# USB.net
KiCad netlist of a schematic drawn in Altium Designer
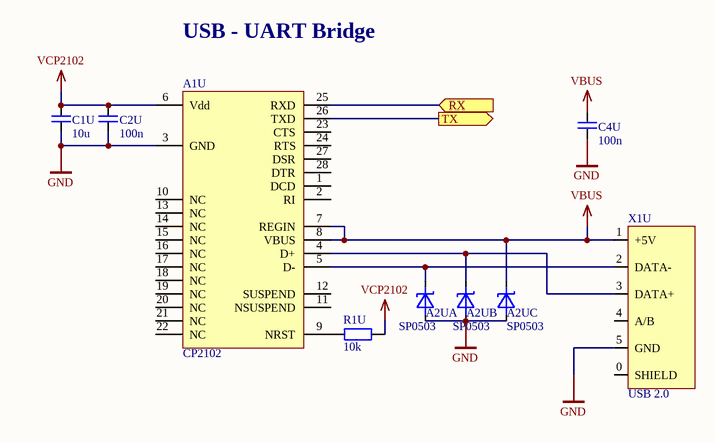
[diagram p0: USB.SchDoc]

(export (version "E")
  (design (tool "Eeschema 10.0.6"))
  (components
    (comp (ref "A1U")
      (value "CP2102")
      (footprint "QFN28")
      (description "USB-UART Bridge")
      (libsource (lib "IC") (part "CP2102"))
    )
    (comp (ref "A2U")
      (value "SP0503")
      (footprint "SOT143-4")
      (description "ESD Suppressors")
      (libsource (lib "IC") (part "SP0503"))
    )
    (comp (ref "C1U") (value "10u") (footprint "0805") (libsource (lib "Passive") (part "Kondensator")))
    (comp (ref "C2U") (value "100n") (footprint "0805") (libsource (lib "Passive") (part "Kondensator")))
    (comp (ref "C4U") (value "100n") (footprint "0805") (libsource (lib "Passive") (part "Kondensator")))
    (comp (ref "R1U") (value "10k") (footprint "0805") (libsource (lib "Passive") (part "Widerstand")))
    (comp (ref "X1U")
      (value "USB 2.0")
      (footprint "USB Mini AB")
      (libsource (lib "Connectors") (part "USB 2.0"))
    )
  )
  (nets
    (net (code "1") (name "/RX") (class "Default")
      (node (ref "A1U") (pin "25") (pinfunction "RXD_25") (pintype "passive"))
    )
    (net (code "2") (name "/TX") (class "Default")
      (node (ref "A1U") (pin "26") (pinfunction "TXD_26") (pintype "passive"))
    )
    (net (code "3") (name "GND") (class "Default")
      (node (ref "A1U") (pin "3") (pinfunction "GND_3") (pintype "passive"))
      (node (ref "A2U") (pin "1") (pinfunction "Annode_1") (pintype "passive"))
      (node (ref "C1U") (pin "1") (pinfunction "1_1") (pintype "passive"))
      (node (ref "C2U") (pin "1") (pinfunction "1_1") (pintype "passive"))
      (node (ref "C4U") (pin "1") (pinfunction "1_1") (pintype "passive"))
      (node (ref "X1U") (pin "5") (pinfunction "GND_5") (pintype "passive"))
    )
    (net (code "4") (name "Net-(A1U-D+)") (class "Default")
      (node (ref "A1U") (pin "4") (pinfunction "D+_4") (pintype "passive"))
      (node (ref "A2U") (pin "3") (pinfunction "K3_3") (pintype "passive"))
      (node (ref "X1U") (pin "3") (pinfunction "DATA+_3") (pintype "passive"))
    )
    (net (code "5") (name "Net-(A1U-D-)") (class "Default")
      (node (ref "A1U") (pin "5") (pinfunction "D-_5") (pintype "passive"))
      (node (ref "A2U") (pin "2") (pinfunction "K1_2") (pintype "passive"))
      (node (ref "X1U") (pin "2") (pinfunction "DATA-_2") (pintype "passive"))
    )
    (net (code "6") (name "Net-(A1U-NRST)") (class "Default")
      (node (ref "A1U") (pin "9") (pinfunction "NRST_9") (pintype "passive"))
      (node (ref "R1U") (pin "1") (pinfunction "1_1") (pintype "passive"))
    )
    (net (code "7") (name "VBUS") (class "Default")
      (node (ref "A1U") (pin "7") (pinfunction "REGIN_7") (pintype "passive"))
      (node (ref "A1U") (pin "8") (pinfunction "VBUS_8") (pintype "passive"))
      (node (ref "A2U") (pin "4") (pinfunction "K3_4") (pintype "passive"))
      (node (ref "C4U") (pin "2") (pinfunction "2_2") (pintype "passive"))
      (node (ref "X1U") (pin "1") (pinfunction "+5V_1") (pintype "passive"))
    )
    (net (code "8") (name "VCP2102") (class "Default")
      (node (ref "A1U") (pin "6") (pinfunction "Vdd_6") (pintype "passive"))
      (node (ref "C1U") (pin "2") (pinfunction "2_2") (pintype "passive"))
      (node (ref "C2U") (pin "2") (pinfunction "2_2") (pintype "passive"))
      (node (ref "R1U") (pin "2") (pinfunction "2_2") (pintype "passive"))
    )
    (net (code "9") (name "unconnected-(A1U-CTS-Pad23)") (class "Default")
      (node (ref "A1U") (pin "23") (pinfunction "CTS_23") (pintype "passive"))
    )
    (net (code "10") (name "unconnected-(A1U-DCD-Pad1)") (class "Default")
      (node (ref "A1U") (pin "1") (pinfunction "DCD_1") (pintype "passive"))
    )
    (net (code "11") (name "unconnected-(A1U-DSR-Pad27)") (class "Default")
      (node (ref "A1U") (pin "27") (pinfunction "DSR_27") (pintype "passive"))
    )
    (net (code "12") (name "unconnected-(A1U-DTR-Pad28)") (class "Default")
      (node (ref "A1U") (pin "28") (pinfunction "DTR_28") (pintype "passive"))
    )
    (net (code "13") (name "unconnected-(A1U-NC-Pad10)") (class "Default")
      (node (ref "A1U") (pin "10") (pinfunction "NC_10") (pintype "passive"))
    )
    (net (code "14") (name "unconnected-(A1U-NC-Pad13)") (class "Default")
      (node (ref "A1U") (pin "13") (pinfunction "NC_13") (pintype "passive"))
    )
    (net (code "15") (name "unconnected-(A1U-NC-Pad14)") (class "Default")
      (node (ref "A1U") (pin "14") (pinfunction "NC_14") (pintype "passive"))
    )
    (net (code "16") (name "unconnected-(A1U-NC-Pad15)") (class "Default")
      (node (ref "A1U") (pin "15") (pinfunction "NC_15") (pintype "passive"))
    )
    (net (code "17") (name "unconnected-(A1U-NC-Pad16)") (class "Default")
      (node (ref "A1U") (pin "16") (pinfunction "NC_16") (pintype "passive"))
    )
    (net (code "18") (name "unconnected-(A1U-NC-Pad17)") (class "Default")
      (node (ref "A1U") (pin "17") (pinfunction "NC_17") (pintype "passive"))
    )
    (net (code "19") (name "unconnected-(A1U-NC-Pad18)") (class "Default")
      (node (ref "A1U") (pin "18") (pinfunction "NC_18") (pintype "passive"))
    )
    (net (code "20") (name "unconnected-(A1U-NC-Pad19)") (class "Default")
      (node (ref "A1U") (pin "19") (pinfunction "NC_19") (pintype "passive"))
    )
    (net (code "21") (name "unconnected-(A1U-NC-Pad20)") (class "Default")
      (node (ref "A1U") (pin "20") (pinfunction "NC_20") (pintype "passive"))
    )
    (net (code "22") (name "unconnected-(A1U-NC-Pad21)") (class "Default")
      (node (ref "A1U") (pin "21") (pinfunction "NC_21") (pintype "passive"))
    )
    (net (code "23") (name "unconnected-(A1U-NC-Pad22)") (class "Default")
      (node (ref "A1U") (pin "22") (pinfunction "NC_22") (pintype "passive"))
    )
    (net (code "24") (name "unconnected-(A1U-NSUSPEND-Pad11)") (class "Default")
      (node (ref "A1U") (pin "11") (pinfunction "NSUSPEND_11") (pintype "passive"))
    )
    (net (code "25") (name "unconnected-(A1U-RI-Pad2)") (class "Default")
      (node (ref "A1U") (pin "2") (pinfunction "RI_2") (pintype "passive"))
    )
    (net (code "26") (name "unconnected-(A1U-RTS-Pad24)") (class "Default")
      (node (ref "A1U") (pin "24") (pinfunction "RTS_24") (pintype "passive"))
    )
    (net (code "27") (name "unconnected-(A1U-SUSPEND-Pad12)") (class "Default")
      (node (ref "A1U") (pin "12") (pinfunction "SUSPEND_12") (pintype "passive"))
    )
    (net (code "28") (name "unconnected-(X1U-A{slash}B-Pad4)") (class "Default")
      (node (ref "X1U") (pin "4") (pinfunction "A/B_4") (pintype "passive"))
    )
    (net (code "29") (name "unconnected-(X1U-SHIELD-Pad0)") (class "Default")
      (node (ref "X1U") (pin "0") (pinfunction "SHIELD_0") (pintype "passive"))
    )
  )
)
